# Memory.net
KiCad netlist of a schematic drawn in Altium Designer
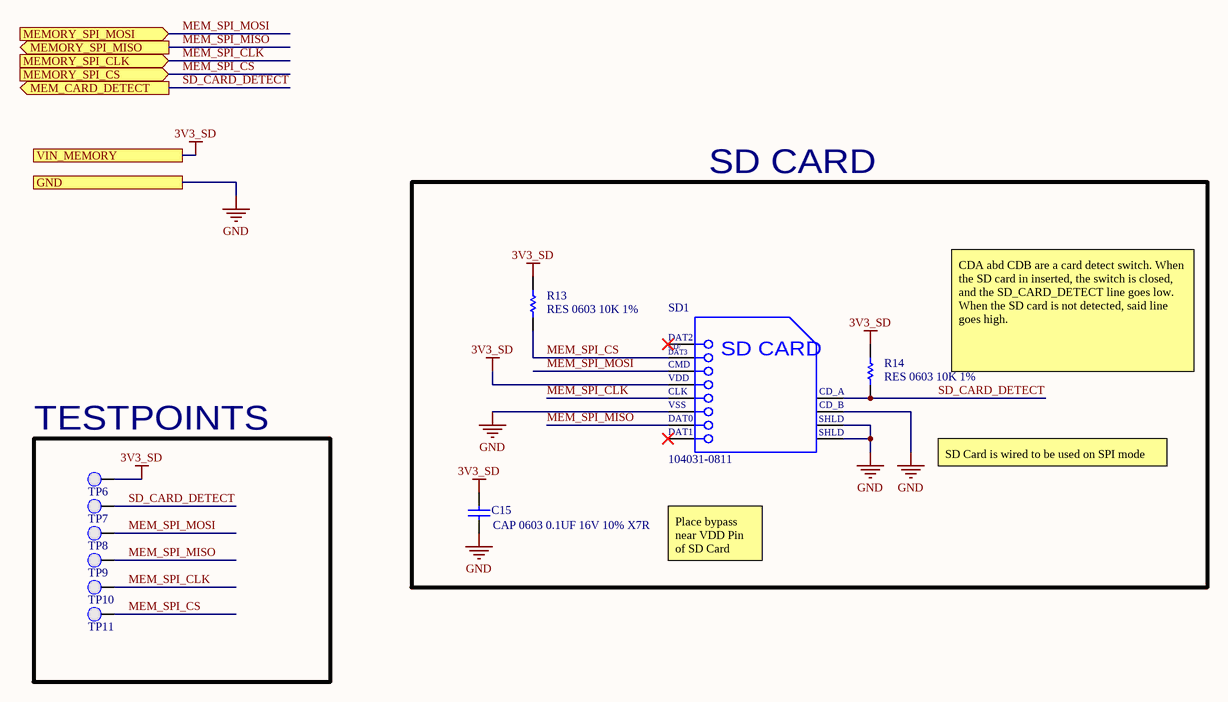
[diagram p0: Memory.SchDoc]

(export (version "E")
  (design (tool "Eeschema 10.0.6"))
  (components
    (comp (ref "C15")
      (value "CAP 0603 0.1UF 16V 10% X7R")
      (footprint "0603_CAP")
      (description "Capacitor Surface Mount 0603 Footprint 0.1UF 16V 10% Tolerance Ceramic X7R")
      (fields (field (name "VOLTAGE") "16V") (field (name "MANUFACTURER") "Various"))
      (libsource (lib "University of Pennsylvania (ESE Labs)") (part "cap"))
    )
    (comp (ref "R13")
      (value "RES 0603 10K 1%")
      (footprint "0603_RES")
      (description "Resistor Surface Mount, 10K Ohms, 0603 Footprint, 1% Tolerance 0.1W")
      (fields (field (name "TOLERANCE") "1%") (field (name "MANUFACTURER") "Various"))
      (libsource (lib "University of Pennsylvania (ESE Labs)") (part "res"))
    )
    (comp (ref "R14")
      (value "RES 0603 10K 1%")
      (footprint "0603_RES")
      (description "Resistor Surface Mount, 10K Ohms, 0603 Footprint, 1% Tolerance 0.1W")
      (fields (field (name "TOLERANCE") "1%") (field (name "MANUFACTURER") "Various"))
      (libsource (lib "University of Pennsylvania (ESE Labs)") (part "res"))
    )
    (comp (ref "SD1")
      (value "104031-0811")
      (footprint "MOLX-104031-0811_V")
      (description "Micro SD Card, RA, -25 to 85 degC, 8-Pin SMD, RoHS, Tape and Reel")
      (fields (field (name "MANUFACTURER") "Molex"))
      (libsource (lib "Altium Content Vault") (part "CN-SD-8-2SW-2S"))
    )
    (comp (ref "TP6")
      (value "Test Point 0.1\"")
      (footprint "Test Point 0.1\"-Footprint-1")
      (libsource (lib "University of Pennsylvania (ESE Labs)") (part "Test Point 0.1{dblquote}-Symbol-1"))
    )
    (comp (ref "TP7")
      (value "Test Point 0.1\"")
      (footprint "Test Point 0.1\"-Footprint-1")
      (libsource (lib "University of Pennsylvania (ESE Labs)") (part "Test Point 0.1{dblquote}-Symbol-1"))
    )
    (comp (ref "TP8")
      (value "Test Point 0.1\"")
      (footprint "Test Point 0.1\"-Footprint-1")
      (libsource (lib "University of Pennsylvania (ESE Labs)") (part "Test Point 0.1{dblquote}-Symbol-1"))
    )
    (comp (ref "TP9")
      (value "Test Point 0.1\"")
      (footprint "Test Point 0.1\"-Footprint-1")
      (libsource (lib "University of Pennsylvania (ESE Labs)") (part "Test Point 0.1{dblquote}-Symbol-1"))
    )
    (comp (ref "TP10")
      (value "Test Point 0.1\"")
      (footprint "Test Point 0.1\"-Footprint-1")
      (libsource (lib "University of Pennsylvania (ESE Labs)") (part "Test Point 0.1{dblquote}-Symbol-1"))
    )
    (comp (ref "TP11")
      (value "Test Point 0.1\"")
      (footprint "Test Point 0.1\"-Footprint-1")
      (libsource (lib "University of Pennsylvania (ESE Labs)") (part "Test Point 0.1{dblquote}-Symbol-1"))
    )
  )
  (nets
    (net (code "1") (name "/MEM_SPI_CLK") (class "Default")
      (node (ref "SD1") (pin "5") (pinfunction "CLK_5") (pintype "passive"))
      (node (ref "TP10") (pin "1") (pinfunction "PAD_1") (pintype "passive"))
    )
    (net (code "2") (name "/MEM_SPI_CS") (class "Default")
      (node (ref "R13") (pin "1") (pinfunction "1_1") (pintype "passive"))
      (node (ref "SD1") (pin "2") (pinfunction "CMD_2") (pintype "passive"))
      (node (ref "TP11") (pin "1") (pinfunction "PAD_1") (pintype "passive"))
    )
    (net (code "3") (name "/MEM_SPI_MISO") (class "Default")
      (node (ref "SD1") (pin "7") (pinfunction "DAT0_7") (pintype "passive"))
      (node (ref "TP9") (pin "1") (pinfunction "PAD_1") (pintype "passive"))
    )
    (net (code "4") (name "/MEM_SPI_MOSI") (class "Default")
      (node (ref "SD1") (pin "3") (pinfunction "VSS1_3") (pintype "passive"))
      (node (ref "TP8") (pin "1") (pinfunction "PAD_1") (pintype "passive"))
    )
    (net (code "5") (name "/SD_CARD_DETECT") (class "Default")
      (node (ref "R14") (pin "1") (pinfunction "1_1") (pintype "passive"))
      (node (ref "SD1") (pin "9") (pinfunction "CD_A_9") (pintype "passive"))
      (node (ref "TP7") (pin "1") (pinfunction "PAD_1") (pintype "passive"))
    )
    (net (code "6") (name "3V3_SD") (class "Default")
      (node (ref "C15") (pin "2") (pinfunction "2_2") (pintype "passive"))
      (node (ref "R13") (pin "2") (pinfunction "2_2") (pintype "passive"))
      (node (ref "R14") (pin "2") (pinfunction "2_2") (pintype "passive"))
      (node (ref "SD1") (pin "4") (pinfunction "VDD_4") (pintype "passive"))
      (node (ref "TP6") (pin "1") (pinfunction "PAD_1") (pintype "passive"))
    )
    (net (code "7") (name "GND") (class "Default")
      (node (ref "C15") (pin "1") (pinfunction "1_1") (pintype "passive"))
      (node (ref "SD1") (pin "10") (pinfunction "CD_B_10") (pintype "passive"))
      (node (ref "SD1") (pin "11") (pinfunction "SHLD1_11") (pintype "passive"))
      (node (ref "SD1") (pin "12") (pinfunction "SHLD2_12") (pintype "passive"))
      (node (ref "SD1") (pin "6") (pinfunction "VSS2_6") (pintype "passive"))
    )
    (net (code "8") (name "unconnected-(SD1-CD{slash}DAT3-Pad1)") (class "Default")
      (node (ref "SD1") (pin "1") (pinfunction "CD/DAT3_1") (pintype "passive+no_connect"))
    )
    (net (code "9") (name "unconnected-(SD1-DAT1-Pad8)") (class "Default")
      (node (ref "SD1") (pin "8") (pinfunction "DAT1_8") (pintype "passive+no_connect"))
    )
  )
)
